# jtag-stlink2-breakout.net
KiCad netlist of a schematic drawn in EAGLE
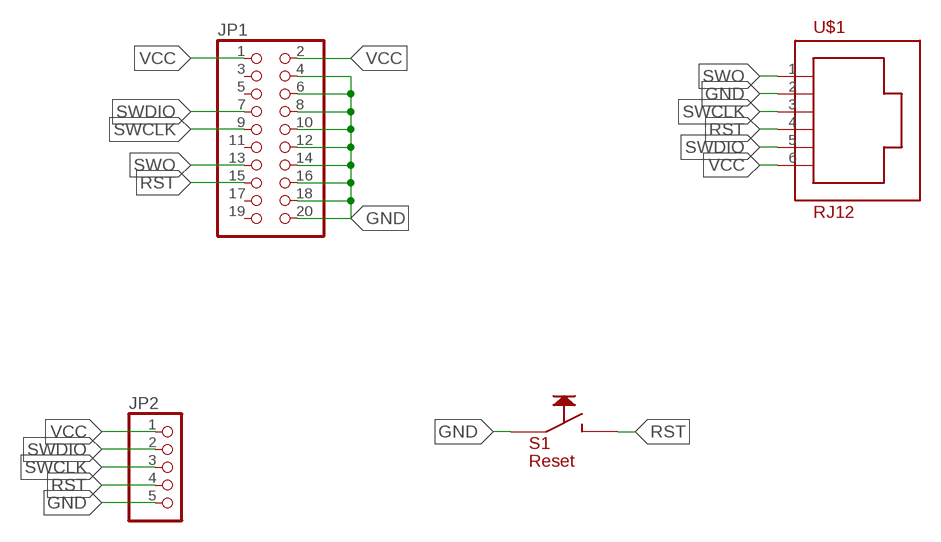
[diagram p0: schematic, sheet 1]

(export (version "E")
  (design (tool "Eeschema 10.0.6"))
  (components
    (comp (ref "JP1")
      (value "PINHD-2X10")
      (footprint "eagle-import:2X10")
      (libsource (lib "eagle-import") (part "PINHD-2X10"))
    )
    (comp (ref "JP2")
      (value "PINHD-1X5")
      (footprint "eagle-import:1X05")
      (libsource (lib "eagle-import") (part "PINHD-1X5"))
    )
    (comp (ref "S1")
      (value "Reset")
      (footprint "eagle-import:SMD-PUSH-BUTTON-ILS-3X6X2,5")
      (libsource (lib "eagle-import") (part "SMD-PUSH-BUTTONILS-3X6X2,5"))
    )
    (comp (ref "U$1")
      (value "RJ12")
      (footprint "eagle-import:RJ12")
      (libsource (lib "eagle-import") (part "RJ12"))
    )
  )
  (nets
    (net (code "1") (name "GND") (class "Default")
      (node (ref "JP1") (pin "10") (pinfunction "10_10") (pintype "passive"))
      (node (ref "JP1") (pin "12") (pinfunction "12_12") (pintype "passive"))
      (node (ref "JP1") (pin "14") (pinfunction "14_14") (pintype "passive"))
      (node (ref "JP1") (pin "16") (pinfunction "16_16") (pintype "passive"))
      (node (ref "JP1") (pin "18") (pinfunction "18_18") (pintype "passive"))
      (node (ref "JP1") (pin "20") (pinfunction "20_20") (pintype "passive"))
      (node (ref "JP1") (pin "4") (pinfunction "4_4") (pintype "passive"))
      (node (ref "JP1") (pin "6") (pinfunction "6_6") (pintype "passive"))
      (node (ref "JP1") (pin "8") (pinfunction "8_8") (pintype "passive"))
      (node (ref "JP2") (pin "5") (pinfunction "5_5") (pintype "passive"))
      (node (ref "S1") (pin "P$1") (pinfunction "P$1_P$1") (pintype "bidirectional"))
      (node (ref "U$1") (pin "2") (pinfunction "2_2") (pintype "bidirectional"))
    )
    (net (code "2") (name "RST") (class "Default")
      (node (ref "JP1") (pin "15") (pinfunction "15_15") (pintype "passive"))
      (node (ref "JP2") (pin "4") (pinfunction "4_4") (pintype "passive"))
      (node (ref "S1") (pin "P$2") (pinfunction "P$2_P$2") (pintype "bidirectional"))
      (node (ref "U$1") (pin "4") (pinfunction "4_4") (pintype "bidirectional"))
    )
    (net (code "3") (name "SWCLK") (class "Default")
      (node (ref "JP1") (pin "9") (pinfunction "9_9") (pintype "passive"))
      (node (ref "JP2") (pin "3") (pinfunction "3_3") (pintype "passive"))
      (node (ref "U$1") (pin "3") (pinfunction "3_3") (pintype "bidirectional"))
    )
    (net (code "4") (name "SWDIO") (class "Default")
      (node (ref "JP1") (pin "7") (pinfunction "7_7") (pintype "passive"))
      (node (ref "JP2") (pin "2") (pinfunction "2_2") (pintype "passive"))
      (node (ref "U$1") (pin "5") (pinfunction "5_5") (pintype "bidirectional"))
    )
    (net (code "5") (name "SWO") (class "Default")
      (node (ref "JP1") (pin "13") (pinfunction "13_13") (pintype "passive"))
      (node (ref "U$1") (pin "1") (pinfunction "1_1") (pintype "bidirectional"))
    )
    (net (code "6") (name "VCC") (class "Default")
      (node (ref "JP1") (pin "1") (pinfunction "1_1") (pintype "passive"))
      (node (ref "JP1") (pin "2") (pinfunction "2_2") (pintype "passive"))
      (node (ref "JP2") (pin "1") (pinfunction "1_1") (pintype "passive"))
      (node (ref "U$1") (pin "6") (pinfunction "6_6") (pintype "bidirectional"))
    )
    (net (code "7") (name "unconnected-(JP1-Pad3)") (class "Default")
      (node (ref "JP1") (pin "3") (pinfunction "3_3") (pintype "passive"))
    )
    (net (code "8") (name "unconnected-(JP1-Pad5)") (class "Default")
      (node (ref "JP1") (pin "5") (pinfunction "5_5") (pintype "passive"))
    )
    (net (code "9") (name "unconnected-(JP1-Pad11)") (class "Default")
      (node (ref "JP1") (pin "11") (pinfunction "11_11") (pintype "passive"))
    )
    (net (code "10") (name "unconnected-(JP1-Pad17)") (class "Default")
      (node (ref "JP1") (pin "17") (pinfunction "17_17") (pintype "passive"))
    )
    (net (code "11") (name "unconnected-(JP1-Pad19)") (class "Default")
      (node (ref "JP1") (pin "19") (pinfunction "19_19") (pintype "passive"))
    )
  )
)
